# 1000BASET1_MEDIA_CONVERTER.net
KiCad netlist of a schematic drawn in Altium Designer
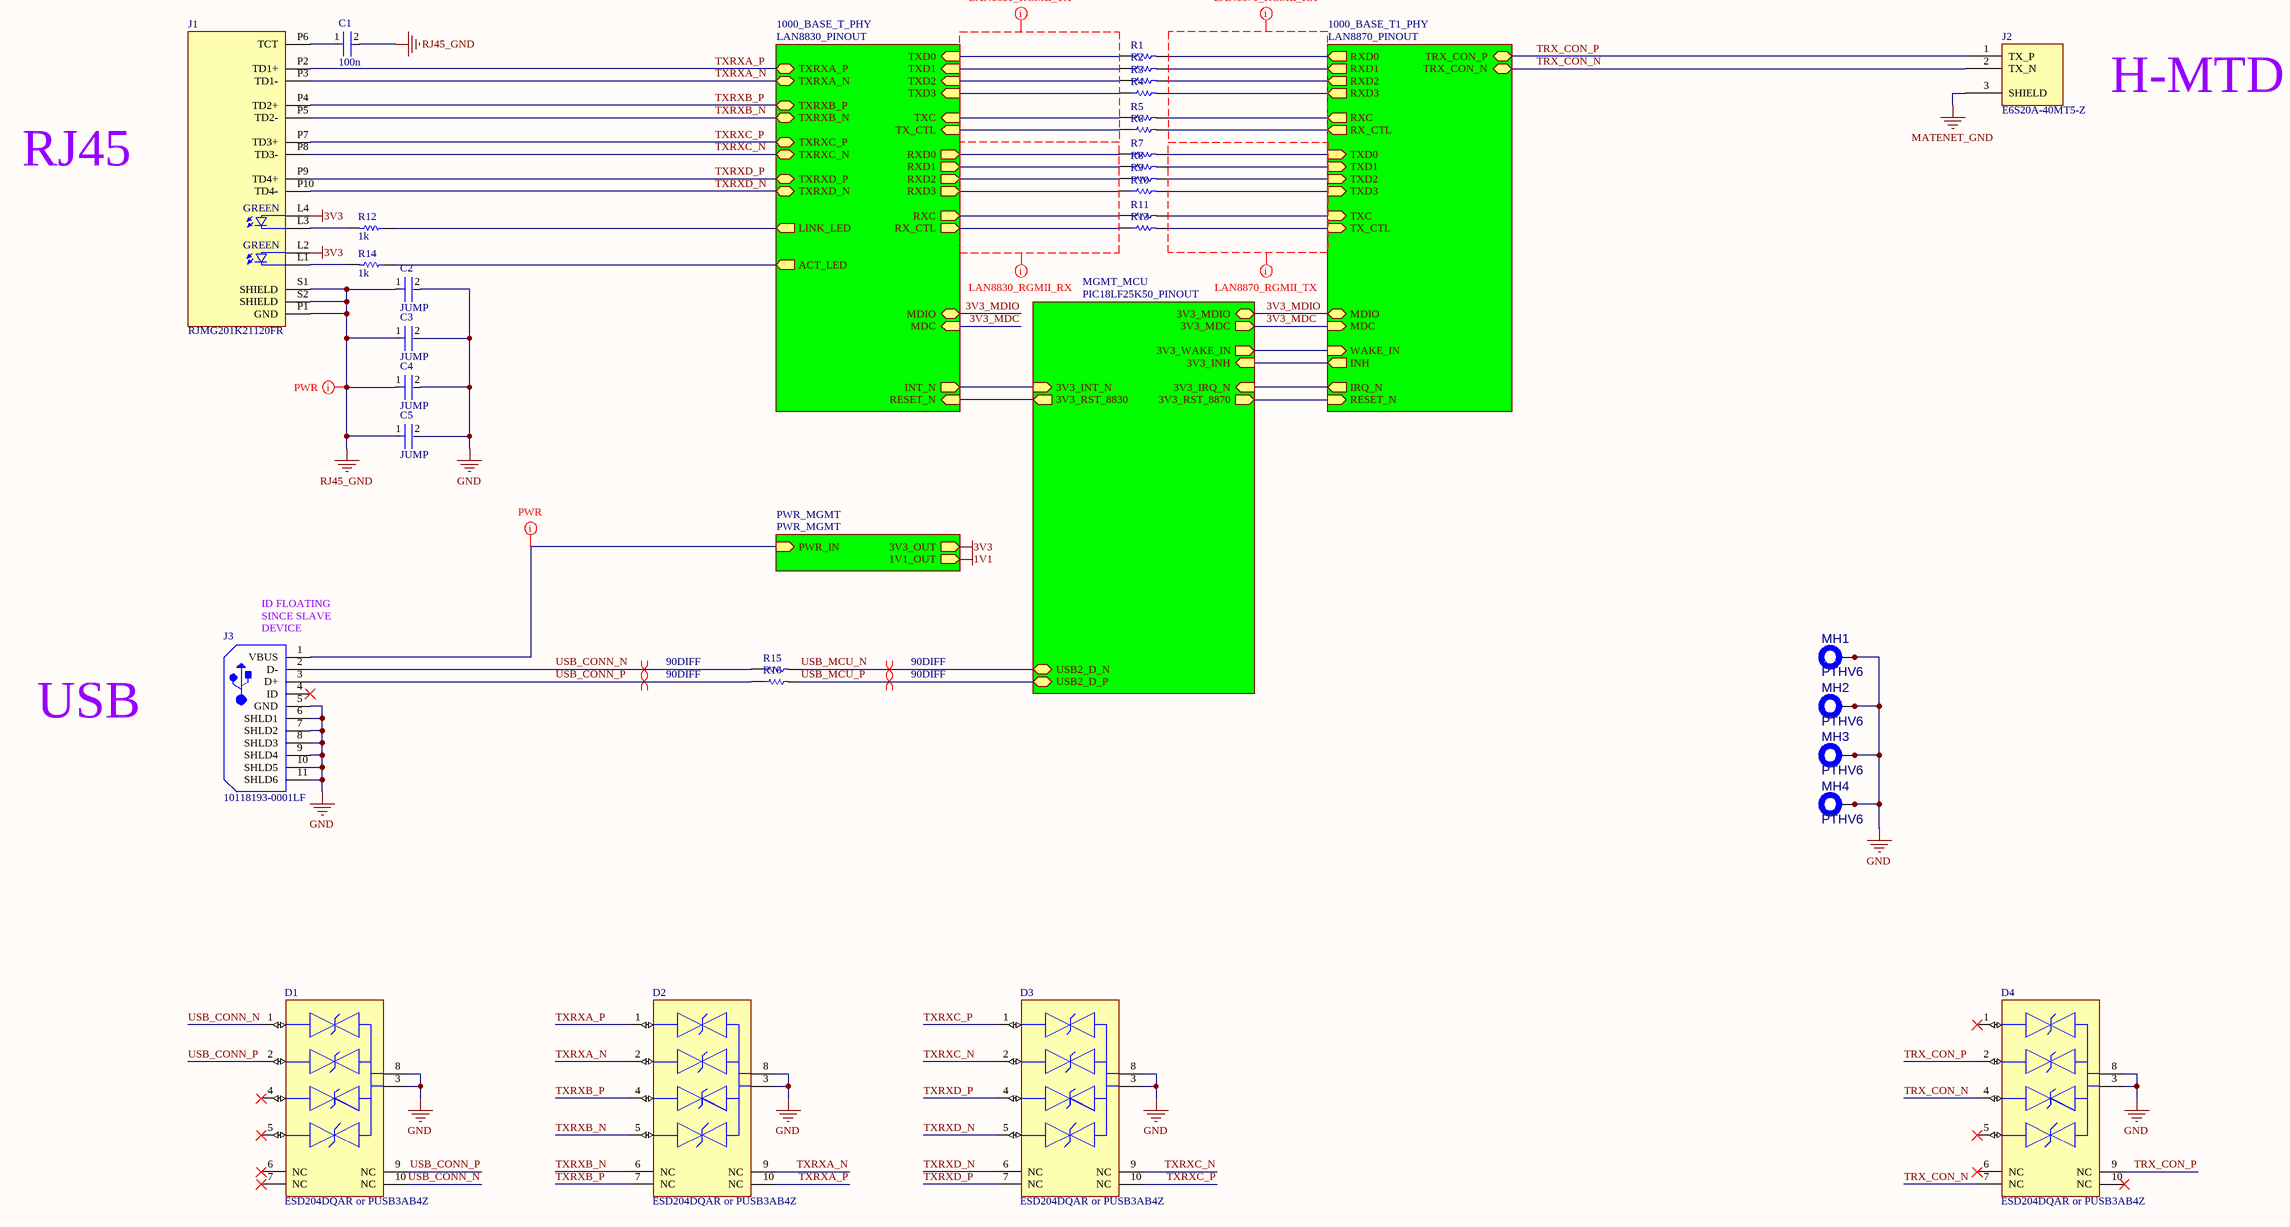
[diagram p0: 1000BASET1_MEDIA_CONVERTER.SchDoc]

(export (version "E")
  (design (tool "Eeschema 10.0.6"))
  (components
    (comp (ref "C1")
      (value "100n")
      (footprint "FP-0402-L_1_0_0_05-W_0_5-IPC_A")
      (description "LARGE PADS, 0402 CAP, CHANGE COMMENT TO MATCH REAL P/N")
      (libsource (lib "Space Concordia") (part "b4654b650e69147ec39a6b967a45e02"))
    )
    (comp (ref "C2")
      (value "JUMP")
      (footprint "FP-0402-L_1_0_0_05-W_0_5-IPC_A")
      (description "LARGE PADS, 0402 CAP, CHANGE COMMENT TO MATCH REAL P/N")
      (libsource (lib "Space Concordia") (part "b4654b650e69147ec39a6b967a45e02"))
    )
    (comp (ref "C3")
      (value "JUMP")
      (footprint "FP-0402-L_1_0_0_05-W_0_5-IPC_A")
      (description "LARGE PADS, 0402 CAP, CHANGE COMMENT TO MATCH REAL P/N")
      (libsource (lib "Space Concordia") (part "b4654b650e69147ec39a6b967a45e02"))
    )
    (comp (ref "C4")
      (value "JUMP")
      (footprint "FP-0402-L_1_0_0_05-W_0_5-IPC_A")
      (description "LARGE PADS, 0402 CAP, CHANGE COMMENT TO MATCH REAL P/N")
      (libsource (lib "Space Concordia") (part "b4654b650e69147ec39a6b967a45e02"))
    )
    (comp (ref "C5")
      (value "JUMP")
      (footprint "FP-0402-L_1_0_0_05-W_0_5-IPC_A")
      (description "LARGE PADS, 0402 CAP, CHANGE COMMENT TO MATCH REAL P/N")
      (libsource (lib "Space Concordia") (part "b4654b650e69147ec39a6b967a45e02"))
    )
    (comp (ref "D1")
      (value "ESD204DQAR or PUSB3AB4Z")
      (footprint "FP-DQA0010A-MFG")
      (description "4-CHANNEL LOW-CAPACITANCE SURGE")
      (fields
        (field (name "MANUFACTURER") "Texas Instruments")
        (field (name "OCTOPART") "https://octopart.com/esd204dqar-texas+instruments-89917476")
      )
      (libsource (lib "Altium Content Vault") (part "1465e58c1818c7767b55926832f0bf5"))
    )
    (comp (ref "D2")
      (value "ESD204DQAR or PUSB3AB4Z")
      (footprint "FP-DQA0010A-MFG")
      (description "4-CHANNEL LOW-CAPACITANCE SURGE")
      (fields
        (field (name "MANUFACTURER") "Texas Instruments")
        (field (name "OCTOPART") "https://octopart.com/esd204dqar-texas+instruments-89917476")
      )
      (libsource (lib "Altium Content Vault") (part "1465e58c1818c7767b55926832f0bf5"))
    )
    (comp (ref "D3")
      (value "ESD204DQAR or PUSB3AB4Z")
      (footprint "FP-DQA0010A-MFG")
      (description "4-CHANNEL LOW-CAPACITANCE SURGE")
      (fields
        (field (name "MANUFACTURER") "Texas Instruments")
        (field (name "OCTOPART") "https://octopart.com/esd204dqar-texas+instruments-89917476")
      )
      (libsource (lib "Altium Content Vault") (part "1465e58c1818c7767b55926832f0bf5"))
    )
    (comp (ref "D4")
      (value "ESD204DQAR or PUSB3AB4Z")
      (footprint "FP-DQA0010A-MFG")
      (description "4-CHANNEL LOW-CAPACITANCE SURGE")
      (fields
        (field (name "MANUFACTURER") "Texas Instruments")
        (field (name "OCTOPART") "https://octopart.com/esd204dqar-texas+instruments-89917476")
      )
      (libsource (lib "Altium Content Vault") (part "1465e58c1818c7767b55926832f0bf5"))
    )
    (comp (ref "J1")
      (value "RJMG201K21120FR")
      (footprint "RJMG201K21120FR-Footprint-1")
      (description "Connector RJ45 Receptacle 8 Position Solder Straight Through Hole 1 Port Tray")
      (libsource (lib "Space Concordia") (part "RJMG201K21120FR"))
    )
    (comp (ref "J2")
      (value "E6S20A-40MT5-Z")
      (footprint "E6S20A-40MT5-Z-Footprint-1")
      (description "RF Connector, 2 Contact(s), Male, Panel Mount, Board And Panel Mount, Solder Terminal, Plug")
      (libsource (lib "Space Concordia") (part "E6S20A-40MT5-Z"))
    )
    (comp (ref "J3")
      (value "10118193-0001LF")
      (footprint "FCI-10118193-0001LF-5_V")
      (description "Micro USB B Type Receptacle, -55 to 85 degC, 5-Pin SMD, RoHS, Tape and Reel")
      (fields (field (name "MANUFACTURER") "FCI"))
      (libsource (lib "Altium Content Vault") (part "USB-5-6SHLD"))
    )
    (comp (ref "MH1")
      (value "PTHV6")
      (footprint "PTHV6 M2")
      (libsource (lib "Space Concordia") (part "PTHV6"))
    )
    (comp (ref "MH2")
      (value "PTHV6")
      (footprint "PTHV6 M2")
      (libsource (lib "Space Concordia") (part "PTHV6"))
    )
    (comp (ref "MH3")
      (value "PTHV6")
      (footprint "PTHV6 M2")
      (libsource (lib "Space Concordia") (part "PTHV6"))
    )
    (comp (ref "MH4")
      (value "PTHV6")
      (footprint "PTHV6 M2")
      (libsource (lib "Space Concordia") (part "PTHV6"))
    )
    (comp (ref "R1")
      (value "0402 JUMPER")
      (footprint "RESC1005X40X25ML05T05")
      (description "READ THE NAME")
      (libsource (lib "Space Concordia") (part "CMP-009-00206-2"))
    )
    (comp (ref "R2")
      (value "0402 JUMPER")
      (footprint "RESC1005X40X25ML05T05")
      (description "READ THE NAME")
      (libsource (lib "Space Concordia") (part "CMP-009-00206-2"))
    )
    (comp (ref "R3")
      (value "0402 JUMPER")
      (footprint "RESC1005X40X25ML05T05")
      (description "READ THE NAME")
      (libsource (lib "Space Concordia") (part "CMP-009-00206-2"))
    )
    (comp (ref "R4")
      (value "0402 JUMPER")
      (footprint "RESC1005X40X25ML05T05")
      (description "READ THE NAME")
      (libsource (lib "Space Concordia") (part "CMP-009-00206-2"))
    )
    (comp (ref "R5")
      (value "0402 JUMPER")
      (footprint "RESC1005X40X25ML05T05")
      (description "READ THE NAME")
      (libsource (lib "Space Concordia") (part "CMP-009-00206-2"))
    )
    (comp (ref "R6")
      (value "0402 JUMPER")
      (footprint "RESC1005X40X25ML05T05")
      (description "READ THE NAME")
      (libsource (lib "Space Concordia") (part "CMP-009-00206-2"))
    )
    (comp (ref "R7")
      (value "0402 JUMPER")
      (footprint "RESC1005X40X25ML05T05")
      (description "READ THE NAME")
      (libsource (lib "Space Concordia") (part "CMP-009-00206-2"))
    )
    (comp (ref "R8")
      (value "0402 JUMPER")
      (footprint "RESC1005X40X25ML05T05")
      (description "READ THE NAME")
      (libsource (lib "Space Concordia") (part "CMP-009-00206-2"))
    )
    (comp (ref "R9")
      (value "0402 JUMPER")
      (footprint "RESC1005X40X25ML05T05")
      (description "READ THE NAME")
      (libsource (lib "Space Concordia") (part "CMP-009-00206-2"))
    )
    (comp (ref "R10")
      (value "0402 JUMPER")
      (footprint "RESC1005X40X25ML05T05")
      (description "READ THE NAME")
      (libsource (lib "Space Concordia") (part "CMP-009-00206-2"))
    )
    (comp (ref "R11")
      (value "0402 JUMPER")
      (footprint "RESC1005X40X25ML05T05")
      (description "READ THE NAME")
      (libsource (lib "Space Concordia") (part "CMP-009-00206-2"))
    )
    (comp (ref "R12")
      (value "1k")
      (footprint "R0603B")
      (description "Resistor")
      (libsource (lib "Space Concordia") (part "Resistor"))
    )
    (comp (ref "R13")
      (value "0402 JUMPER")
      (footprint "RESC1005X40X25ML05T05")
      (description "READ THE NAME")
      (libsource (lib "Space Concordia") (part "CMP-009-00206-2"))
    )
    (comp (ref "R14")
      (value "1k")
      (footprint "R0603B")
      (description "Resistor")
      (libsource (lib "Space Concordia") (part "Resistor"))
    )
    (comp (ref "R15")
      (value "0402 JUMPER")
      (footprint "RESC1005X40X25ML05T05")
      (description "READ THE NAME")
      (libsource (lib "Space Concordia") (part "CMP-009-00206-2"))
    )
    (comp (ref "R16")
      (value "0402 JUMPER")
      (footprint "RESC1005X40X25ML05T05")
      (description "READ THE NAME")
      (libsource (lib "Space Concordia") (part "CMP-009-00206-2"))
    )
  )
  (nets
    (net (code "6") (name "/ACT_LED") (class "Default")
      (node (ref "R14") (pin "1") (pinfunction "1_1") (pintype "passive"))
    )
    (net (code "10") (name "/LINK_LED") (class "Default")
      (node (ref "R12") (pin "1") (pinfunction "1_1") (pintype "passive"))
    )
    (net (code "11") (name "/PWR_IN") (class "Default")
      (node (ref "J3") (pin "1") (pinfunction "VBUS_1") (pintype "passive"))
    )
    (net (code "12") (name "/RXC") (class "Default")
      (node (ref "R5") (pin "2") (pinfunction "2_2") (pintype "passive"))
    )
    (net (code "13") (name "/RXC_1") (class "Default")
      (node (ref "R11") (pin "1") (pinfunction "1_1") (pintype "passive"))
    )
    (net (code "14") (name "/RXD0") (class "Default")
      (node (ref "R1") (pin "2") (pinfunction "2_2") (pintype "passive"))
    )
    (net (code "15") (name "/RXD0_1") (class "Default")
      (node (ref "R7") (pin "1") (pinfunction "1_1") (pintype "passive"))
    )
    (net (code "16") (name "/RXD1") (class "Default")
      (node (ref "R2") (pin "2") (pinfunction "2_2") (pintype "passive"))
    )
    (net (code "17") (name "/RXD1_1") (class "Default")
      (node (ref "R8") (pin "1") (pinfunction "1_1") (pintype "passive"))
    )
    (net (code "18") (name "/RXD2") (class "Default")
      (node (ref "R3") (pin "2") (pinfunction "2_2") (pintype "passive"))
    )
    (net (code "19") (name "/RXD2_1") (class "Default")
      (node (ref "R9") (pin "1") (pinfunction "1_1") (pintype "passive"))
    )
    (net (code "20") (name "/RXD3") (class "Default")
      (node (ref "R4") (pin "2") (pinfunction "2_2") (pintype "passive"))
    )
    (net (code "21") (name "/RXD3_1") (class "Default")
      (node (ref "R10") (pin "1") (pinfunction "1_1") (pintype "passive"))
    )
    (net (code "22") (name "/RX_CTL") (class "Default")
      (node (ref "R6") (pin "2") (pinfunction "2_2") (pintype "passive"))
    )
    (net (code "23") (name "/RX_CTL_1") (class "Default")
      (node (ref "R13") (pin "1") (pinfunction "1_1") (pintype "passive"))
    )
    (net (code "24") (name "/TRX_CON_N") (class "Default")
      (node (ref "D4") (pin "4") (pinfunction "IO3_4") (pintype "bidirectional"))
      (node (ref "D4") (pin "7") (pinfunction "NC_7") (pintype "passive"))
      (node (ref "J2") (pin "2") (pinfunction "TX_N_2") (pintype "passive"))
    )
    (net (code "25") (name "/TRX_CON_P") (class "Default")
      (node (ref "D4") (pin "2") (pinfunction "IO2_2") (pintype "bidirectional"))
      (node (ref "D4") (pin "9") (pinfunction "NC_9") (pintype "passive"))
      (node (ref "J2") (pin "1") (pinfunction "TX_P_1") (pintype "passive"))
    )
    (net (code "26") (name "/TXC") (class "Default")
      (node (ref "R11") (pin "2") (pinfunction "2_2") (pintype "passive"))
    )
    (net (code "27") (name "/TXC_1") (class "Default")
      (node (ref "R5") (pin "1") (pinfunction "1_1") (pintype "passive"))
    )
    (net (code "28") (name "/TXD0") (class "Default")
      (node (ref "R7") (pin "2") (pinfunction "2_2") (pintype "passive"))
    )
    (net (code "29") (name "/TXD0_1") (class "Default")
      (node (ref "R1") (pin "1") (pinfunction "1_1") (pintype "passive"))
    )
    (net (code "30") (name "/TXD1") (class "Default")
      (node (ref "R8") (pin "2") (pinfunction "2_2") (pintype "passive"))
    )
    (net (code "31") (name "/TXD1_1") (class "Default")
      (node (ref "R2") (pin "1") (pinfunction "1_1") (pintype "passive"))
    )
    (net (code "32") (name "/TXD2") (class "Default")
      (node (ref "R9") (pin "2") (pinfunction "2_2") (pintype "passive"))
    )
    (net (code "33") (name "/TXD2_1") (class "Default")
      (node (ref "R3") (pin "1") (pinfunction "1_1") (pintype "passive"))
    )
    (net (code "34") (name "/TXD3") (class "Default")
      (node (ref "R10") (pin "2") (pinfunction "2_2") (pintype "passive"))
    )
    (net (code "35") (name "/TXD3_1") (class "Default")
      (node (ref "R4") (pin "1") (pinfunction "1_1") (pintype "passive"))
    )
    (net (code "36") (name "/TXRXA_N") (class "Default")
      (node (ref "D2") (pin "2") (pinfunction "IO2_2") (pintype "bidirectional"))
      (node (ref "D2") (pin "9") (pinfunction "NC_9") (pintype "passive"))
      (node (ref "J1") (pin "P3") (pinfunction "TD1-_P3") (pintype "passive"))
    )
    (net (code "37") (name "/TXRXA_P") (class "Default")
      (node (ref "D2") (pin "1") (pinfunction "IO1_1") (pintype "bidirectional"))
      (node (ref "D2") (pin "10") (pinfunction "NC_10") (pintype "passive"))
      (node (ref "J1") (pin "P2") (pinfunction "TD1+_P2") (pintype "passive"))
    )
    (net (code "38") (name "/TXRXB_N") (class "Default")
      (node (ref "D2") (pin "5") (pinfunction "IO4_5") (pintype "bidirectional"))
      (node (ref "D2") (pin "6") (pinfunction "NC_6") (pintype "passive"))
      (node (ref "J1") (pin "P5") (pinfunction "TD2-_P5") (pintype "passive"))
    )
    (net (code "39") (name "/TXRXB_P") (class "Default")
      (node (ref "D2") (pin "4") (pinfunction "IO3_4") (pintype "bidirectional"))
      (node (ref "D2") (pin "7") (pinfunction "NC_7") (pintype "passive"))
      (node (ref "J1") (pin "P4") (pinfunction "TD2+_P4") (pintype "passive"))
    )
    (net (code "40") (name "/TXRXC_N") (class "Default")
      (node (ref "D3") (pin "2") (pinfunction "IO2_2") (pintype "bidirectional"))
      (node (ref "D3") (pin "9") (pinfunction "NC_9") (pintype "passive"))
      (node (ref "J1") (pin "P8") (pinfunction "TD3-_P8") (pintype "passive"))
    )
    (net (code "41") (name "/TXRXC_P") (class "Default")
      (node (ref "D3") (pin "1") (pinfunction "IO1_1") (pintype "bidirectional"))
      (node (ref "D3") (pin "10") (pinfunction "NC_10") (pintype "passive"))
      (node (ref "J1") (pin "P7") (pinfunction "TD3+_P7") (pintype "passive"))
    )
    (net (code "42") (name "/TXRXD_N") (class "Default")
      (node (ref "D3") (pin "5") (pinfunction "IO4_5") (pintype "bidirectional"))
      (node (ref "D3") (pin "6") (pinfunction "NC_6") (pintype "passive"))
      (node (ref "J1") (pin "P10") (pinfunction "TD4-_P10") (pintype "passive"))
    )
    (net (code "43") (name "/TXRXD_P") (class "Default")
      (node (ref "D3") (pin "4") (pinfunction "IO3_4") (pintype "bidirectional"))
      (node (ref "D3") (pin "7") (pinfunction "NC_7") (pintype "passive"))
      (node (ref "J1") (pin "P9") (pinfunction "TD4+_P9") (pintype "passive"))
    )
    (net (code "44") (name "/TX_CTL") (class "Default")
      (node (ref "R13") (pin "2") (pinfunction "2_2") (pintype "passive"))
    )
    (net (code "45") (name "/TX_CTL_1") (class "Default")
      (node (ref "R6") (pin "1") (pinfunction "1_1") (pintype "passive"))
    )
    (net (code "46") (name "/USB_CONN_N") (class "Default")
      (node (ref "D1") (pin "1") (pinfunction "IO1_1") (pintype "bidirectional"))
      (node (ref "D1") (pin "10") (pinfunction "NC_10") (pintype "passive"))
      (node (ref "J3") (pin "2") (pinfunction "D-_2") (pintype "passive"))
      (node (ref "R15") (pin "1") (pinfunction "1_1") (pintype "passive"))
    )
    (net (code "47") (name "/USB_CONN_P") (class "Default")
      (node (ref "D1") (pin "2") (pinfunction "IO2_2") (pintype "bidirectional"))
      (node (ref "D1") (pin "9") (pinfunction "NC_9") (pintype "passive"))
      (node (ref "J3") (pin "3") (pinfunction "D+_3") (pintype "passive"))
      (node (ref "R16") (pin "1") (pinfunction "1_1") (pintype "passive"))
    )
    (net (code "48") (name "/USB_MCU_N") (class "Default")
      (node (ref "R15") (pin "2") (pinfunction "2_2") (pintype "passive"))
    )
    (net (code "49") (name "/USB_MCU_P") (class "Default")
      (node (ref "R16") (pin "2") (pinfunction "2_2") (pintype "passive"))
    )
    (net (code "51") (name "3V3") (class "Default")
      (node (ref "J1") (pin "L2") (pinfunction "L2_L2") (pintype "passive"))
      (node (ref "J1") (pin "L4") (pinfunction "L4_L4") (pintype "passive"))
    )
    (net (code "52") (name "GND") (class "Default")
      (node (ref "C2") (pin "2") (pinfunction "2_2") (pintype "passive"))
      (node (ref "C3") (pin "2") (pinfunction "2_2") (pintype "passive"))
      (node (ref "C4") (pin "2") (pinfunction "2_2") (pintype "passive"))
      (node (ref "C5") (pin "2") (pinfunction "2_2") (pintype "passive"))
      (node (ref "D1") (pin "3") (pinfunction "GND_3") (pintype "power_in"))
      (node (ref "D1") (pin "8") (pinfunction "GND_8") (pintype "power_in"))
      (node (ref "D2") (pin "3") (pinfunction "GND_3") (pintype "power_in"))
      (node (ref "D2") (pin "8") (pinfunction "GND_8") (pintype "power_in"))
      (node (ref "D3") (pin "3") (pinfunction "GND_3") (pintype "power_in"))
      (node (ref "D3") (pin "8") (pinfunction "GND_8") (pintype "power_in"))
      (node (ref "D4") (pin "3") (pinfunction "GND_3") (pintype "power_in"))
      (node (ref "D4") (pin "8") (pinfunction "GND_8") (pintype "power_in"))
      (node (ref "J3") (pin "10") (pinfunction "SHLD5_10") (pintype "passive"))
      (node (ref "J3") (pin "11") (pinfunction "SHLD6_11") (pintype "passive"))
      (node (ref "J3") (pin "5") (pinfunction "GND_5") (pintype "passive"))
      (node (ref "J3") (pin "6") (pinfunction "SHLD1_6") (pintype "passive"))
      (node (ref "J3") (pin "7") (pinfunction "SHLD2_7") (pintype "passive"))
      (node (ref "J3") (pin "8") (pinfunction "SHLD3_8") (pintype "passive"))
      (node (ref "J3") (pin "9") (pinfunction "SHLD4_9") (pintype "passive"))
      (node (ref "MH1") (pin "1") (pinfunction "MH_1") (pintype "passive"))
      (node (ref "MH1") (pin "2") (pinfunction "V1_2") (pintype "passive"))
      (node (ref "MH1") (pin "3") (pinfunction "V2_3") (pintype "passive"))
      (node (ref "MH1") (pin "4") (pinfunction "V3_4") (pintype "passive"))
      (node (ref "MH1") (pin "5") (pinfunction "V4_5") (pintype "passive"))
      (node (ref "MH1") (pin "6") (pinfunction "V5_6") (pintype "passive"))
      (node (ref "MH1") (pin "7") (pinfunction "V6_7") (pintype "passive"))
      (node (ref "MH2") (pin "1") (pinfunction "MH_1") (pintype "passive"))
      (node (ref "MH2") (pin "2") (pinfunction "V1_2") (pintype "passive"))
      (node (ref "MH2") (pin "3") (pinfunction "V2_3") (pintype "passive"))
      (node (ref "MH2") (pin "4") (pinfunction "V3_4") (pintype "passive"))
      (node (ref "MH2") (pin "5") (pinfunction "V4_5") (pintype "passive"))
      (node (ref "MH2") (pin "6") (pinfunction "V5_6") (pintype "passive"))
      (node (ref "MH2") (pin "7") (pinfunction "V6_7") (pintype "passive"))
      (node (ref "MH3") (pin "1") (pinfunction "MH_1") (pintype "passive"))
      (node (ref "MH3") (pin "2") (pinfunction "V1_2") (pintype "passive"))
      (node (ref "MH3") (pin "3") (pinfunction "V2_3") (pintype "passive"))
      (node (ref "MH3") (pin "4") (pinfunction "V3_4") (pintype "passive"))
      (node (ref "MH3") (pin "5") (pinfunction "V4_5") (pintype "passive"))
      (node (ref "MH3") (pin "6") (pinfunction "V5_6") (pintype "passive"))
      (node (ref "MH3") (pin "7") (pinfunction "V6_7") (pintype "passive"))
      (node (ref "MH4") (pin "1") (pinfunction "MH_1") (pintype "passive"))
      (node (ref "MH4") (pin "2") (pinfunction "V1_2") (pintype "passive"))
      (node (ref "MH4") (pin "3") (pinfunction "V2_3") (pintype "passive"))
      (node (ref "MH4") (pin "4") (pinfunction "V3_4") (pintype "passive"))
      (node (ref "MH4") (pin "5") (pinfunction "V4_5") (pintype "passive"))
      (node (ref "MH4") (pin "6") (pinfunction "V5_6") (pintype "passive"))
      (node (ref "MH4") (pin "7") (pinfunction "V6_7") (pintype "passive"))
    )
    (net (code "53") (name "MATENET_GND") (class "Default")
      (node (ref "J2") (pin "3") (pinfunction "SHIELD_3") (pintype "passive"))
    )
    (net (code "54") (name "Net-(J1-PadL1)") (class "Default")
      (node (ref "J1") (pin "L1") (pinfunction "L1_L1") (pintype "passive"))
      (node (ref "R14") (pin "2") (pinfunction "2_2") (pintype "passive"))
    )
    (net (code "55") (name "Net-(J1-PadL3)") (class "Default")
      (node (ref "J1") (pin "L3") (pinfunction "L3_L3") (pintype "passive"))
      (node (ref "R12") (pin "2") (pinfunction "2_2") (pintype "passive"))
    )
    (net (code "56") (name "Net-(J1-TCT)") (class "Default")
      (node (ref "C1") (pin "1") (pinfunction "1_1") (pintype "passive"))
      (node (ref "J1") (pin "P6") (pinfunction "TCT_P6") (pintype "passive"))
    )
    (net (code "57") (name "RJ45_GND") (class "Default")
      (node (ref "C1") (pin "2") (pinfunction "2_2") (pintype "passive"))
      (node (ref "C2") (pin "1") (pinfunction "1_1") (pintype "passive"))
      (node (ref "C3") (pin "1") (pinfunction "1_1") (pintype "passive"))
      (node (ref "C4") (pin "1") (pinfunction "1_1") (pintype "passive"))
      (node (ref "C5") (pin "1") (pinfunction "1_1") (pintype "passive"))
      (node (ref "J1") (pin "P1") (pinfunction "GND_P1") (pintype "power_in"))
      (node (ref "J1") (pin "S1") (pinfunction "SHIELD_S1") (pintype "passive"))
      (node (ref "J1") (pin "S2") (pinfunction "SHIELD_S2") (pintype "passive"))
    )
    (net (code "58") (name "unconnected-(D1-IO3-Pad4)") (class "Default")
      (node (ref "D1") (pin "4") (pinfunction "IO3_4") (pintype "bidirectional+no_connect"))
    )
    (net (code "59") (name "unconnected-(D1-IO4-Pad5)") (class "Default")
      (node (ref "D1") (pin "5") (pinfunction "IO4_5") (pintype "bidirectional+no_connect"))
    )
    (net (code "60") (name "unconnected-(D1-NC-Pad6)") (class "Default")
      (node (ref "D1") (pin "6") (pinfunction "NC_6") (pintype "passive+no_connect"))
    )
    (net (code "61") (name "unconnected-(D1-NC-Pad7)") (class "Default")
      (node (ref "D1") (pin "7") (pinfunction "NC_7") (pintype "passive+no_connect"))
    )
    (net (code "62") (name "unconnected-(D4-IO1-Pad1)") (class "Default")
      (node (ref "D4") (pin "1") (pinfunction "IO1_1") (pintype "bidirectional+no_connect"))
    )
    (net (code "63") (name "unconnected-(D4-IO4-Pad5)") (class "Default")
      (node (ref "D4") (pin "5") (pinfunction "IO4_5") (pintype "bidirectional+no_connect"))
    )
    (net (code "64") (name "unconnected-(D4-NC-Pad6)") (class "Default")
      (node (ref "D4") (pin "6") (pinfunction "NC_6") (pintype "passive+no_connect"))
    )
    (net (code "65") (name "unconnected-(D4-NC-Pad10)") (class "Default")
      (node (ref "D4") (pin "10") (pinfunction "NC_10") (pintype "passive+no_connect"))
    )
    (net (code "66") (name "unconnected-(J3-ID-Pad4)") (class "Default")
      (node (ref "J3") (pin "4") (pinfunction "ID_4") (pintype "passive+no_connect"))
    )
  )
)
